# SolarMPPT.net
KiCad netlist of a schematic drawn in EAGLE
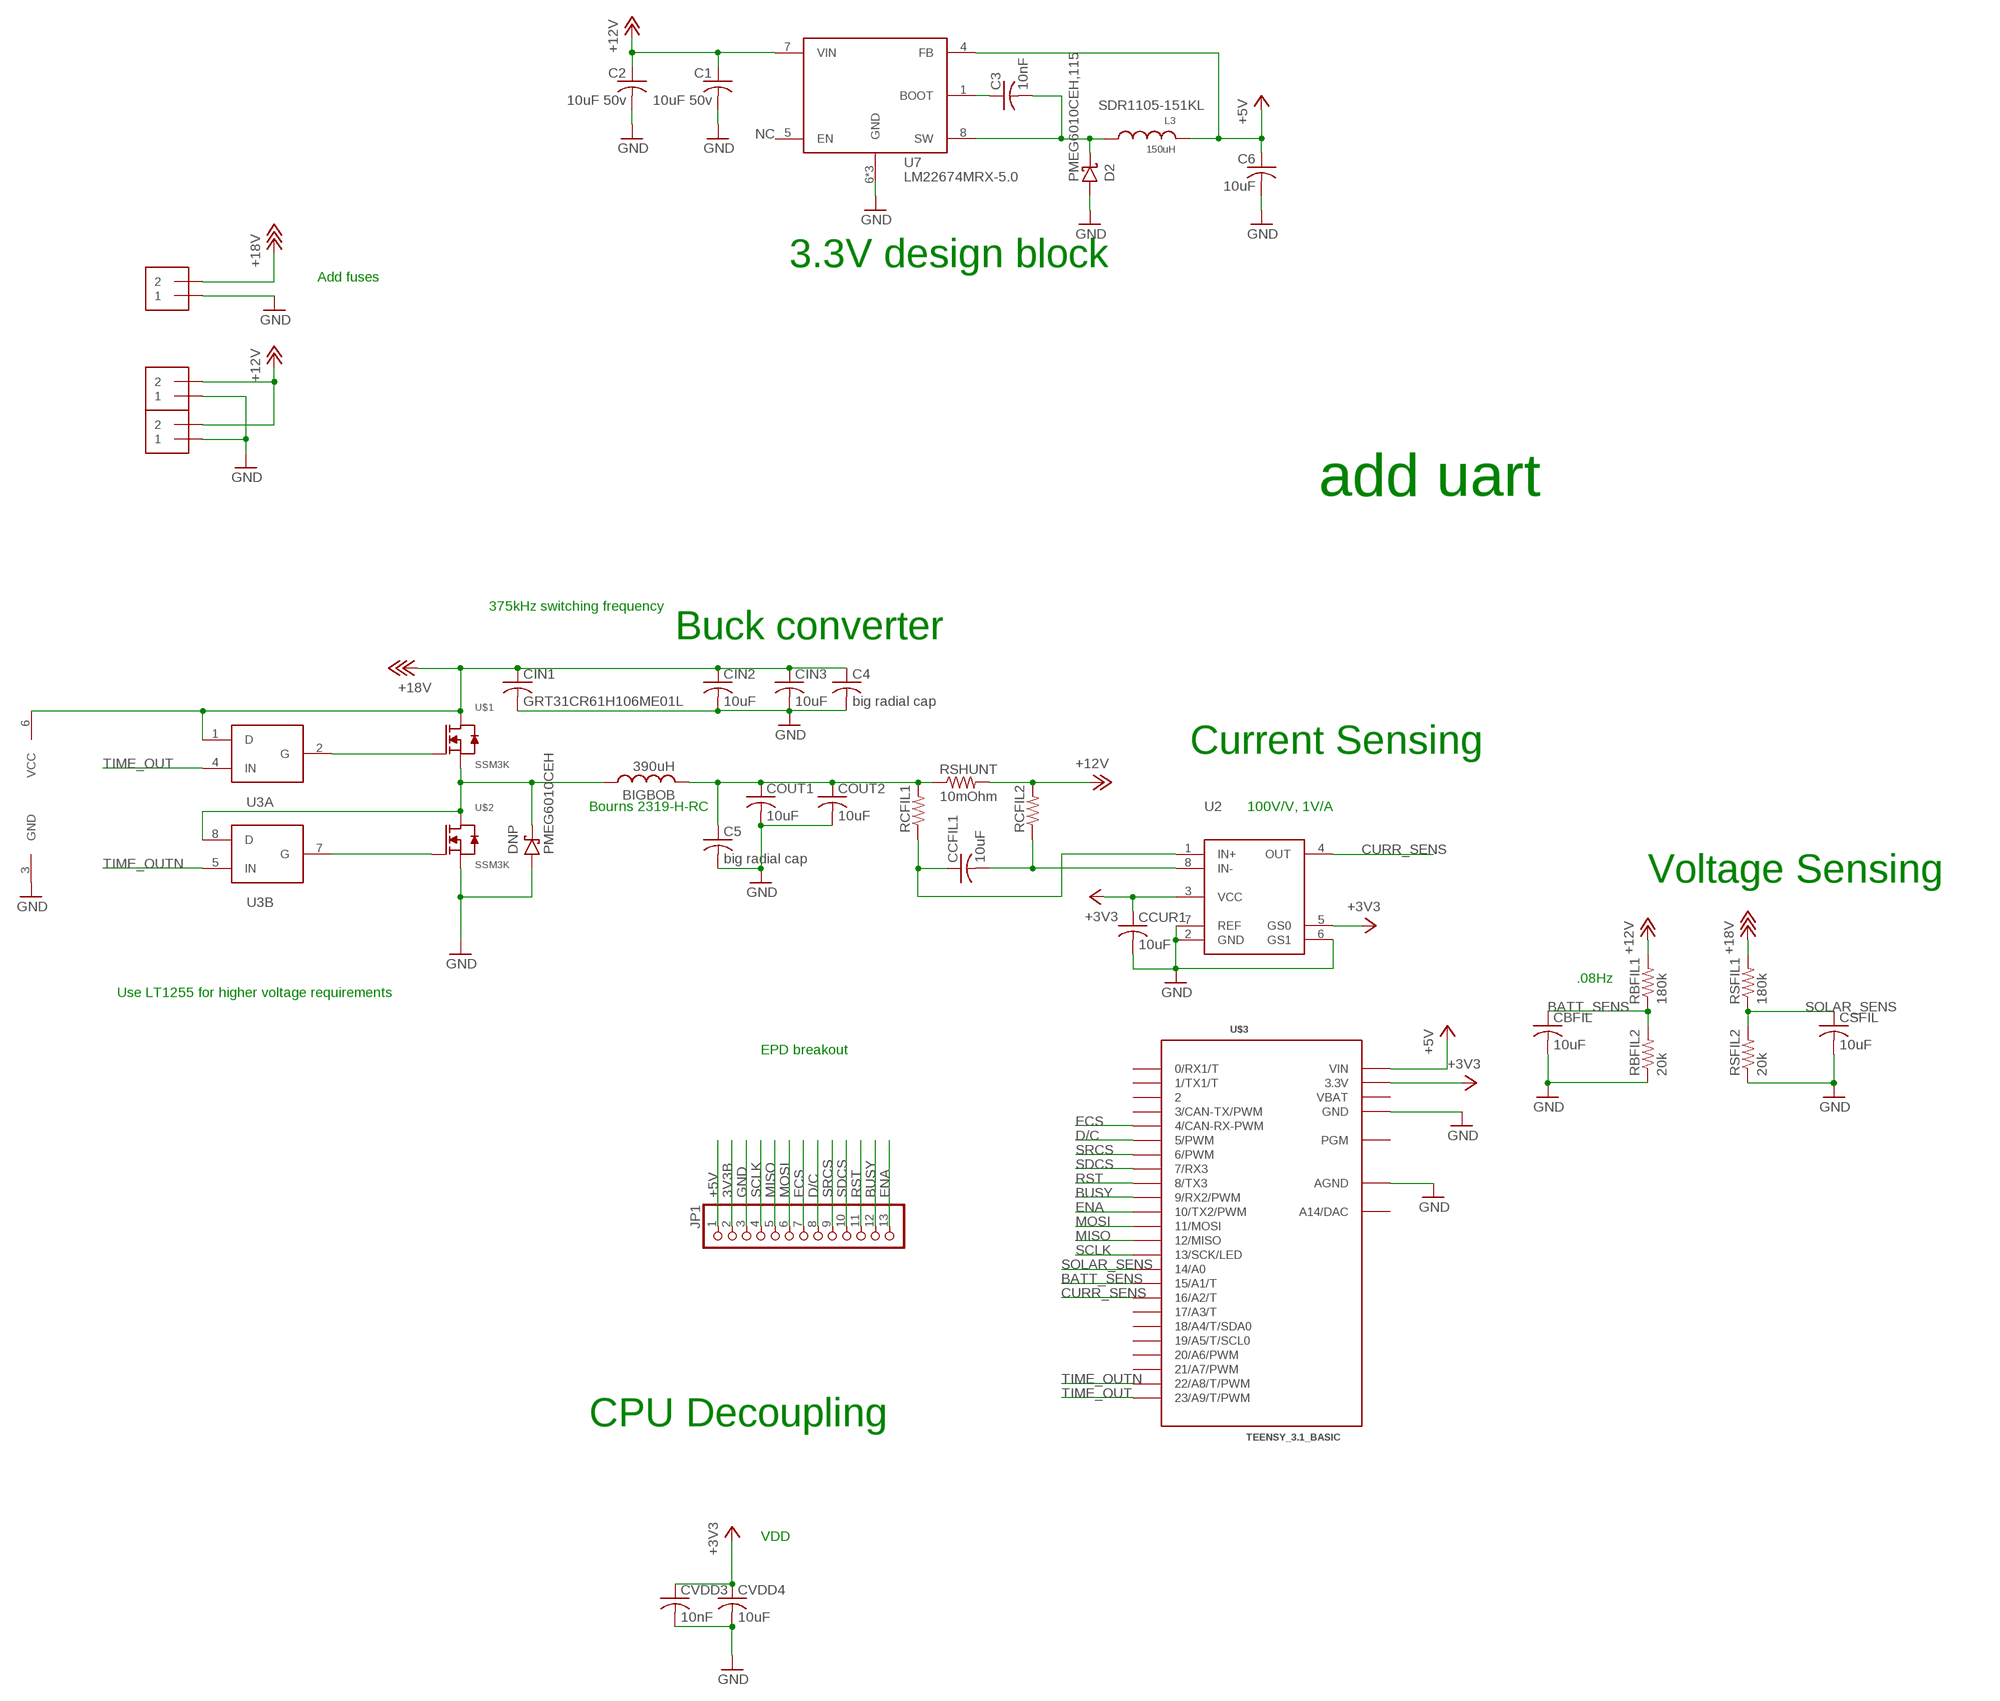
[diagram p0: schematic, sheet 1]

(export (version "E")
  (design (tool "Eeschema 10.0.6"))
  (components
    (comp (ref "BIGBOB")
      (value "390uH")
      (footprint "eagle-import:TJ6-U2")
      (libsource (lib "eagle-import") (part "L-USTJ6-U2"))
    )
    (comp (ref "C1")
      (value "10uF 50v")
      (footprint "eagle-import:C0805")
      (fields (field (name "PARTNO") "UMK212BJ105KG-T"))
      (libsource (lib "eagle-import") (part "C-USC0805"))
    )
    (comp (ref "C2")
      (value "10uF 50v")
      (footprint "eagle-import:C1206")
      (fields (field (name "PARTNO") "GRM31CR71H475KA12L"))
      (libsource (lib "eagle-import") (part "C-USC1206"))
    )
    (comp (ref "C3")
      (value "10nF")
      (footprint "eagle-import:C0805")
      (fields (field (name "PARTNO") "GRM216R71H103KA01D"))
      (libsource (lib "eagle-import") (part "C-USC0805"))
    )
    (comp (ref "C4")
      (value "big radial cap")
      (footprint "eagle-import:C050-024X044")
      (libsource (lib "eagle-import") (part "rcl_334_C-US050-024X044"))
    )
    (comp (ref "C5")
      (value "big radial cap")
      (footprint "eagle-import:C050-024X044")
      (libsource (lib "eagle-import") (part "rcl_334_C-US050-024X044"))
    )
    (comp (ref "C6")
      (value "10uF")
      (footprint "eagle-import:C0805")
      (fields (field (name "PARTNO") "GRM21BR61E106KA73L"))
      (libsource (lib "eagle-import") (part "C-USC0805"))
    )
    (comp (ref "CBFIL")
      (value "10uF")
      (footprint "eagle-import:C0805")
      (libsource (lib "eagle-import") (part "rcl_334_C-USC0805"))
    )
    (comp (ref "CCFIL1")
      (value "10uF")
      (footprint "eagle-import:C0805")
      (libsource (lib "eagle-import") (part "rcl_334_C-USC0805"))
    )
    (comp (ref "CCUR1")
      (value "10uF")
      (footprint "eagle-import:C0805")
      (libsource (lib "eagle-import") (part "rcl_334_C-USC0805"))
    )
    (comp (ref "CIN1")
      (value "GRT31CR61H106ME01L")
      (footprint "eagle-import:C1206")
      (libsource (lib "eagle-import") (part "rcl_334_C-USC1206"))
    )
    (comp (ref "CIN2")
      (value "10uF")
      (footprint "eagle-import:C1206")
      (libsource (lib "eagle-import") (part "rcl_334_C-USC1206"))
    )
    (comp (ref "CIN3")
      (value "10uF")
      (footprint "eagle-import:C1206")
      (libsource (lib "eagle-import") (part "rcl_334_C-USC1206"))
    )
    (comp (ref "COUT1")
      (value "10uF")
      (footprint "eagle-import:C1206")
      (libsource (lib "eagle-import") (part "rcl_334_C-USC1206"))
    )
    (comp (ref "COUT2")
      (value "10uF")
      (footprint "eagle-import:C1206")
      (libsource (lib "eagle-import") (part "rcl_334_C-USC1206"))
    )
    (comp (ref "CSFIL")
      (value "10uF")
      (footprint "eagle-import:C0805")
      (libsource (lib "eagle-import") (part "rcl_334_C-USC0805"))
    )
    (comp (ref "CVDD3")
      (value "10nF")
      (footprint "eagle-import:C0805")
      (libsource (lib "eagle-import") (part "rcl_334_C-USC0805"))
    )
    (comp (ref "CVDD4")
      (value "10uF")
      (footprint "eagle-import:C0805")
      (libsource (lib "eagle-import") (part "rcl_334_C-USC0805"))
    )
    (comp (ref "D2")
      (value "PMEG6010CEH,115")
      (footprint "eagle-import:SOD-123")
      (fields (field (name "PARTNO") "PMEG6010CEH115"))
      (libsource (lib "eagle-import") (part "PMEG6010CEH,115"))
    )
    (comp (ref "DNP")
      (value "PMEG6010CEH")
      (footprint "eagle-import:SOD-123")
      (libsource (lib "eagle-import") (part "MBR0520LT3G"))
    )
    (comp (ref "J2")
      (value "1X2-3.5MM")
      (footprint "eagle-import:1X2-3.5MM")
      (libsource (lib "eagle-import") (part "1X2-3.5MM"))
    )
    (comp (ref "J3")
      (value "1X2-3.5MM")
      (footprint "eagle-import:1X2-3.5MM")
      (libsource (lib "eagle-import") (part "1X2-3.5MM"))
    )
    (comp (ref "J6")
      (value "1X2-3.5MM")
      (footprint "eagle-import:1X2-3.5MM")
      (libsource (lib "eagle-import") (part "1X2-3.5MM"))
    )
    (comp (ref "JP1")
      (value "PINHD-1X13")
      (footprint "eagle-import:1X13")
      (libsource (lib "eagle-import") (part "PINHD-1X13"))
    )
    (comp (ref "L3")
      (value "150uH")
      (footprint "eagle-import:SDR1105")
      (fields (field (name "PARTNO") "SDR1105-151KL"))
      (libsource (lib "eagle-import") (part "SDR1105"))
    )
    (comp (ref "RBFIL1")
      (value "180k")
      (footprint "eagle-import:R0805")
      (libsource (lib "eagle-import") (part "R-US_R0805"))
    )
    (comp (ref "RBFIL2")
      (value "20k")
      (footprint "eagle-import:R0805")
      (libsource (lib "eagle-import") (part "R-US_R0805"))
    )
    (comp (ref "RCFIL1")
      (value "R-US_R0805")
      (footprint "eagle-import:R0805")
      (libsource (lib "eagle-import") (part "R-US_R0805"))
    )
    (comp (ref "RCFIL2")
      (value "R-US_R0805")
      (footprint "eagle-import:R0805")
      (libsource (lib "eagle-import") (part "R-US_R0805"))
    )
    (comp (ref "RSFIL1")
      (value "180k")
      (footprint "eagle-import:R0805")
      (libsource (lib "eagle-import") (part "R-US_R0805"))
    )
    (comp (ref "RSFIL2")
      (value "20k")
      (footprint "eagle-import:R0805")
      (libsource (lib "eagle-import") (part "R-US_R0805"))
    )
    (comp (ref "RSHUNT")
      (value "10mOhm")
      (footprint "eagle-import:R1206")
      (libsource (lib "eagle-import") (part "R-US_R1206"))
    )
    (comp (ref "U$1")
      (value "SSM3K")
      (footprint "eagle-import:SOT-23-MOSFET")
      (libsource (lib "eagle-import") (part "SSM3K"))
    )
    (comp (ref "U$2")
      (value "SSM3K")
      (footprint "eagle-import:SOT-23-MOSFET")
      (libsource (lib "eagle-import") (part "SSM3K"))
    )
    (comp (ref "U$3")
      (value "TEENSY_3.1_BASIC")
      (footprint "eagle-import:TEENSY_3.1_BASIC")
      (libsource (lib "eagle-import") (part "TEENSY_3.1_BASIC"))
    )
    (comp (ref "U2")
      (value "INA225VSSOP")
      (footprint "eagle-import:VSSOP-8")
      (libsource (lib "eagle-import") (part "INA225VSSOP"))
    )
    (comp (ref "U3")
      (value "LTC1155")
      (footprint "eagle-import:LT-SOL8")
      (libsource (lib "eagle-import") (part "LTC1155"))
    )
    (comp (ref "U7")
      (value "LM22674MRX-5.0")
      (footprint "eagle-import:SOIC-8-POWERPAD")
      (fields (field (name "PARTNO") "LM22674MRX-5.0/NOPB"))
      (libsource (lib "eagle-import") (part "LM22674"))
    )
  )
  (nets
    (net (code "1") (name "+3V3") (class "Default")
      (node (ref "CCUR1") (pin "1") (pinfunction "1_1") (pintype "passive"))
      (node (ref "CVDD3") (pin "1") (pinfunction "1_1") (pintype "passive"))
      (node (ref "CVDD4") (pin "1") (pinfunction "1_1") (pintype "passive"))
      (node (ref "U$3") (pin "3.3V") (pinfunction "3.3V_3.3V") (pintype "power_in"))
      (node (ref "U$3") (pin "3.3V1") (pinfunction "3.3V_3.3V1") (pintype "power_in"))
      (node (ref "U2") (pin "3") (pinfunction "VCC_3") (pintype "power_in"))
      (node (ref "U2") (pin "5") (pinfunction "GS0_5") (pintype "input"))
    )
    (net (code "2") (name "+5V") (class "Default")
      (node (ref "C6") (pin "1") (pinfunction "1_1") (pintype "passive"))
      (node (ref "JP1") (pin "1") (pinfunction "1_1") (pintype "passive"))
      (node (ref "L3") (pin "P$1") (pinfunction "P$1_P$1") (pintype "bidirectional"))
      (node (ref "U$3") (pin "VIN") (pinfunction "VIN_VIN") (pintype "power_in"))
      (node (ref "U7") (pin "4") (pinfunction "FB_4") (pintype "bidirectional"))
    )
    (net (code "3") (name "+12V") (class "Default")
      (node (ref "C1") (pin "1") (pinfunction "1_1") (pintype "passive"))
      (node (ref "C2") (pin "1") (pinfunction "1_1") (pintype "passive"))
      (node (ref "J2") (pin "2") (pinfunction "2_2") (pintype "passive"))
      (node (ref "J3") (pin "2") (pinfunction "2_2") (pintype "passive"))
      (node (ref "RBFIL1") (pin "2") (pinfunction "2_2") (pintype "passive"))
      (node (ref "RCFIL2") (pin "2") (pinfunction "2_2") (pintype "passive"))
      (node (ref "RSHUNT") (pin "2") (pinfunction "2_2") (pintype "passive"))
      (node (ref "U7") (pin "7") (pinfunction "VIN_7") (pintype "bidirectional"))
    )
    (net (code "4") (name "+18V") (class "Default")
      (node (ref "C4") (pin "1") (pinfunction "1_1") (pintype "passive"))
      (node (ref "CIN1") (pin "1") (pinfunction "1_1") (pintype "passive"))
      (node (ref "CIN2") (pin "1") (pinfunction "1_1") (pintype "passive"))
      (node (ref "CIN3") (pin "1") (pinfunction "1_1") (pintype "passive"))
      (node (ref "J6") (pin "2") (pinfunction "2_2") (pintype "passive"))
      (node (ref "RSFIL1") (pin "2") (pinfunction "2_2") (pintype "passive"))
      (node (ref "U$1") (pin "D") (pinfunction "D_D") (pintype "bidirectional"))
      (node (ref "U3") (pin "1") (pinfunction "D_1") (pintype "input"))
      (node (ref "U3") (pin "6") (pinfunction "VCC_6") (pintype "power_in"))
    )
    (net (code "5") (name "/3V3B") (class "Default")
      (node (ref "JP1") (pin "2") (pinfunction "2_2") (pintype "passive"))
    )
    (net (code "6") (name "/BATT_SENS") (class "Default")
      (node (ref "CBFIL") (pin "1") (pinfunction "1_1") (pintype "passive"))
      (node (ref "RBFIL1") (pin "1") (pinfunction "1_1") (pintype "passive"))
      (node (ref "RBFIL2") (pin "2") (pinfunction "2_2") (pintype "passive"))
      (node (ref "U$3") (pin "15/A1") (pinfunction "15/A1/T_15/A1") (pintype "bidirectional"))
    )
    (net (code "7") (name "/BUSY") (class "Default")
      (node (ref "JP1") (pin "12") (pinfunction "12_12") (pintype "passive"))
      (node (ref "U$3") (pin "9") (pinfunction "9/RX2/PWM_9") (pintype "bidirectional"))
    )
    (net (code "8") (name "/CURR_SENS") (class "Default")
      (node (ref "U$3") (pin "16/A2") (pinfunction "16/A2/T_16/A2") (pintype "bidirectional"))
      (node (ref "U2") (pin "4") (pinfunction "OUT_4") (pintype "output"))
    )
    (net (code "9") (name "/D{slash}C") (class "Default")
      (node (ref "JP1") (pin "8") (pinfunction "8_8") (pintype "passive"))
      (node (ref "U$3") (pin "5") (pinfunction "5/PWM_5") (pintype "bidirectional"))
    )
    (net (code "10") (name "/ECS") (class "Default")
      (node (ref "JP1") (pin "7") (pinfunction "7_7") (pintype "passive"))
      (node (ref "U$3") (pin "4") (pinfunction "4/CAN-RX-PWM_4") (pintype "bidirectional"))
    )
    (net (code "11") (name "/ENA") (class "Default")
      (node (ref "JP1") (pin "13") (pinfunction "13_13") (pintype "passive"))
      (node (ref "U$3") (pin "10") (pinfunction "10/TX2/PWM_10") (pintype "bidirectional"))
    )
    (net (code "12") (name "/MISO") (class "Default")
      (node (ref "JP1") (pin "5") (pinfunction "5_5") (pintype "passive"))
      (node (ref "U$3") (pin "12") (pinfunction "12/MISO_12") (pintype "bidirectional"))
    )
    (net (code "13") (name "/MOSI") (class "Default")
      (node (ref "JP1") (pin "6") (pinfunction "6_6") (pintype "passive"))
      (node (ref "U$3") (pin "11") (pinfunction "11/MOSI_11") (pintype "bidirectional"))
    )
    (net (code "14") (name "/RST") (class "Default")
      (node (ref "JP1") (pin "11") (pinfunction "11_11") (pintype "passive"))
      (node (ref "U$3") (pin "8") (pinfunction "8/TX3_8") (pintype "bidirectional"))
    )
    (net (code "15") (name "/SCLK") (class "Default")
      (node (ref "JP1") (pin "4") (pinfunction "4_4") (pintype "passive"))
      (node (ref "U$3") (pin "13") (pinfunction "13/SCK/LED_13") (pintype "bidirectional"))
    )
    (net (code "16") (name "/SDCS") (class "Default")
      (node (ref "JP1") (pin "10") (pinfunction "10_10") (pintype "passive"))
      (node (ref "U$3") (pin "7") (pinfunction "7/RX3_7") (pintype "bidirectional"))
    )
    (net (code "17") (name "/SOLAR_SENS") (class "Default")
      (node (ref "CSFIL") (pin "1") (pinfunction "1_1") (pintype "passive"))
      (node (ref "RSFIL1") (pin "1") (pinfunction "1_1") (pintype "passive"))
      (node (ref "RSFIL2") (pin "2") (pinfunction "2_2") (pintype "passive"))
      (node (ref "U$3") (pin "14/A0") (pinfunction "14/A0_14/A0") (pintype "bidirectional"))
    )
    (net (code "18") (name "/SRCS") (class "Default")
      (node (ref "JP1") (pin "9") (pinfunction "9_9") (pintype "passive"))
      (node (ref "U$3") (pin "6") (pinfunction "6/PWM_6") (pintype "bidirectional"))
    )
    (net (code "19") (name "/TIME_OUT") (class "Default")
      (node (ref "U$3") (pin "23/A9") (pinfunction "23/A9/T/PWM_23/A9") (pintype "bidirectional"))
      (node (ref "U3") (pin "4") (pinfunction "IN_4") (pintype "input"))
    )
    (net (code "20") (name "/TIME_OUTN") (class "Default")
      (node (ref "U$3") (pin "22/A8") (pinfunction "22/A8/T/PWM_22/A8") (pintype "bidirectional"))
      (node (ref "U3") (pin "5") (pinfunction "IN_5") (pintype "input"))
    )
    (net (code "21") (name "/VBAT") (class "Default")
      (node (ref "U$3") (pin "VBAT") (pinfunction "VBAT_VBAT") (pintype "power_in"))
    )
    (net (code "22") (name "GND") (class "Default")
      (node (ref "C1") (pin "2") (pinfunction "2_2") (pintype "passive"))
      (node (ref "C2") (pin "2") (pinfunction "2_2") (pintype "passive"))
      (node (ref "C4") (pin "2") (pinfunction "2_2") (pintype "passive"))
      (node (ref "C5") (pin "2") (pinfunction "2_2") (pintype "passive"))
      (node (ref "C6") (pin "2") (pinfunction "2_2") (pintype "passive"))
      (node (ref "CBFIL") (pin "2") (pinfunction "2_2") (pintype "passive"))
      (node (ref "CCUR1") (pin "2") (pinfunction "2_2") (pintype "passive"))
      (node (ref "CIN1") (pin "2") (pinfunction "2_2") (pintype "passive"))
      (node (ref "CIN2") (pin "2") (pinfunction "2_2") (pintype "passive"))
      (node (ref "CIN3") (pin "2") (pinfunction "2_2") (pintype "passive"))
      (node (ref "COUT1") (pin "2") (pinfunction "2_2") (pintype "passive"))
      (node (ref "COUT2") (pin "2") (pinfunction "2_2") (pintype "passive"))
      (node (ref "CSFIL") (pin "2") (pinfunction "2_2") (pintype "passive"))
      (node (ref "CVDD3") (pin "2") (pinfunction "2_2") (pintype "passive"))
      (node (ref "CVDD4") (pin "2") (pinfunction "2_2") (pintype "passive"))
      (node (ref "D2") (pin "A") (pinfunction "A_A") (pintype "bidirectional"))
      (node (ref "DNP") (pin "A") (pinfunction "A_A") (pintype "bidirectional"))
      (node (ref "J2") (pin "1") (pinfunction "1_1") (pintype "passive"))
      (node (ref "J3") (pin "1") (pinfunction "1_1") (pintype "passive"))
      (node (ref "J6") (pin "1") (pinfunction "1_1") (pintype "passive"))
      (node (ref "JP1") (pin "3") (pinfunction "3_3") (pintype "passive"))
      (node (ref "RBFIL2") (pin "1") (pinfunction "1_1") (pintype "passive"))
      (node (ref "RSFIL2") (pin "1") (pinfunction "1_1") (pintype "passive"))
      (node (ref "U$2") (pin "S") (pinfunction "S_S") (pintype "bidirectional"))
      (node (ref "U$3") (pin "AGND") (pinfunction "AGND_AGND") (pintype "power_in"))
      (node (ref "U$3") (pin "GND") (pinfunction "GND_GND") (pintype "power_in"))
      (node (ref "U$3") (pin "GND1") (pinfunction "GND_GND1") (pintype "power_in"))
      (node (ref "U2") (pin "2") (pinfunction "GND_2") (pintype "power_in"))
      (node (ref "U2") (pin "6") (pinfunction "GS1_6") (pintype "input"))
      (node (ref "U2") (pin "7") (pinfunction "REF_7") (pintype "power_in"))
      (node (ref "U3") (pin "3") (pinfunction "GND_3") (pintype "power_in"))
      (node (ref "U7") (pin "6") (pinfunction "GND_6") (pintype "bidirectional"))
      (node (ref "U7") (pin "PAD") (pinfunction "GND_PAD") (pintype "bidirectional"))
      (node (ref "U7") (pin "PAD1") (pinfunction "GND_PAD1") (pintype "bidirectional"))
    )
    (net (code "23") (name "Net-(BIGBOB-Pad2)") (class "Default")
      (node (ref "BIGBOB") (pin "2") (pinfunction "2_2") (pintype "passive"))
      (node (ref "C5") (pin "1") (pinfunction "1_1") (pintype "passive"))
      (node (ref "COUT1") (pin "1") (pinfunction "1_1") (pintype "passive"))
      (node (ref "COUT2") (pin "1") (pinfunction "1_1") (pintype "passive"))
      (node (ref "RCFIL1") (pin "2") (pinfunction "2_2") (pintype "passive"))
      (node (ref "RSHUNT") (pin "1") (pinfunction "1_1") (pintype "passive"))
    )
    (net (code "24") (name "Net-(U2-IN+)") (class "Default")
      (node (ref "CCFIL1") (pin "1") (pinfunction "1_1") (pintype "passive"))
      (node (ref "RCFIL1") (pin "1") (pinfunction "1_1") (pintype "passive"))
      (node (ref "U2") (pin "1") (pinfunction "IN+_1") (pintype "input"))
    )
    (net (code "25") (name "Net-(U2-IN-)") (class "Default")
      (node (ref "CCFIL1") (pin "2") (pinfunction "2_2") (pintype "passive"))
      (node (ref "RCFIL2") (pin "1") (pinfunction "1_1") (pintype "passive"))
      (node (ref "U2") (pin "8") (pinfunction "IN-_8") (pintype "input"))
    )
    (net (code "26") (name "Net-(U3A-G)") (class "Default")
      (node (ref "U$1") (pin "G") (pinfunction "G_G") (pintype "bidirectional"))
      (node (ref "U3") (pin "2") (pinfunction "G_2") (pintype "output"))
    )
    (net (code "27") (name "Net-(U3B-D)") (class "Default")
      (node (ref "BIGBOB") (pin "1") (pinfunction "1_1") (pintype "passive"))
      (node (ref "DNP") (pin "K") (pinfunction "K_K") (pintype "bidirectional"))
      (node (ref "U$1") (pin "S") (pinfunction "S_S") (pintype "bidirectional"))
      (node (ref "U$2") (pin "D") (pinfunction "D_D") (pintype "bidirectional"))
      (node (ref "U3") (pin "8") (pinfunction "D_8") (pintype "input"))
    )
    (net (code "28") (name "Net-(U3B-G)") (class "Default")
      (node (ref "U$2") (pin "G") (pinfunction "G_G") (pintype "bidirectional"))
      (node (ref "U3") (pin "7") (pinfunction "G_7") (pintype "output"))
    )
    (net (code "29") (name "Net-(U7-BOOT)") (class "Default")
      (node (ref "C3") (pin "1") (pinfunction "1_1") (pintype "passive"))
      (node (ref "U7") (pin "1") (pinfunction "BOOT_1") (pintype "bidirectional"))
    )
    (net (code "30") (name "Net-(U7-SW)") (class "Default")
      (node (ref "C3") (pin "2") (pinfunction "2_2") (pintype "passive"))
      (node (ref "D2") (pin "K") (pinfunction "K_K") (pintype "bidirectional"))
      (node (ref "L3") (pin "P$2") (pinfunction "P$2_P$2") (pintype "bidirectional"))
      (node (ref "U7") (pin "8") (pinfunction "SW_8") (pintype "bidirectional"))
    )
    (net (code "31") (name "unconnected-(U$3-0{slash}RX1{slash}T-Pad0)") (class "Default")
      (node (ref "U$3") (pin "0") (pinfunction "0/RX1/T_0") (pintype "bidirectional"))
    )
    (net (code "32") (name "unconnected-(U$3-1{slash}TX1{slash}T-Pad1)") (class "Default")
      (node (ref "U$3") (pin "1") (pinfunction "1/TX1/T_1") (pintype "bidirectional"))
    )
    (net (code "33") (name "unconnected-(U$3-3{slash}CAN-TX{slash}PWM-Pad3)") (class "Default")
      (node (ref "U$3") (pin "3") (pinfunction "3/CAN-TX/PWM_3") (pintype "bidirectional"))
    )
    (net (code "34") (name "unconnected-(U$3-17{slash}A3{slash}T-Pad17{slash}A3)") (class "Default")
      (node (ref "U$3") (pin "17/A3") (pinfunction "17/A3/T_17/A3") (pintype "bidirectional"))
    )
    (net (code "35") (name "unconnected-(U$3-18{slash}A4{slash}T{slash}SDA0-Pad18{slash}A4)") (class "Default")
      (node (ref "U$3") (pin "18/A4") (pinfunction "18/A4/T/SDA0_18/A4") (pintype "bidirectional"))
    )
    (net (code "36") (name "unconnected-(U$3-19{slash}A5{slash}T{slash}SCL0-Pad19{slash}A5)") (class "Default")
      (node (ref "U$3") (pin "19/A5") (pinfunction "19/A5/T/SCL0_19/A5") (pintype "bidirectional"))
    )
    (net (code "37") (name "unconnected-(U$3-20{slash}A6{slash}PWM-Pad20{slash}A6)") (class "Default")
      (node (ref "U$3") (pin "20/A6") (pinfunction "20/A6/PWM_20/A6") (pintype "bidirectional"))
    )
    (net (code "38") (name "unconnected-(U$3-21{slash}A7{slash}PWM-Pad21{slash}A7)") (class "Default")
      (node (ref "U$3") (pin "21/A7") (pinfunction "21/A7/PWM_21/A7") (pintype "bidirectional"))
    )
    (net (code "39") (name "unconnected-(U$3-A14{slash}DAC-PadA14)") (class "Default")
      (node (ref "U$3") (pin "A14") (pinfunction "A14/DAC_A14") (pintype "bidirectional"))
    )
    (net (code "40") (name "unconnected-(U$3-Pad2)") (class "Default")
      (node (ref "U$3") (pin "2") (pinfunction "2_2") (pintype "bidirectional"))
    )
    (net (code "41") (name "unconnected-(U$3-PadPGM)") (class "Default")
      (node (ref "U$3") (pin "PGM") (pinfunction "PGM_PGM") (pintype "bidirectional"))
    )
    (net (code "42") (name "unconnected-(U7-EN-Pad5)") (class "Default")
      (node (ref "U7") (pin "5") (pinfunction "EN_5") (pintype "bidirectional"))
    )
  )
)
